# fsa1_psu.net
KiCad netlist of a schematic drawn in EAGLE
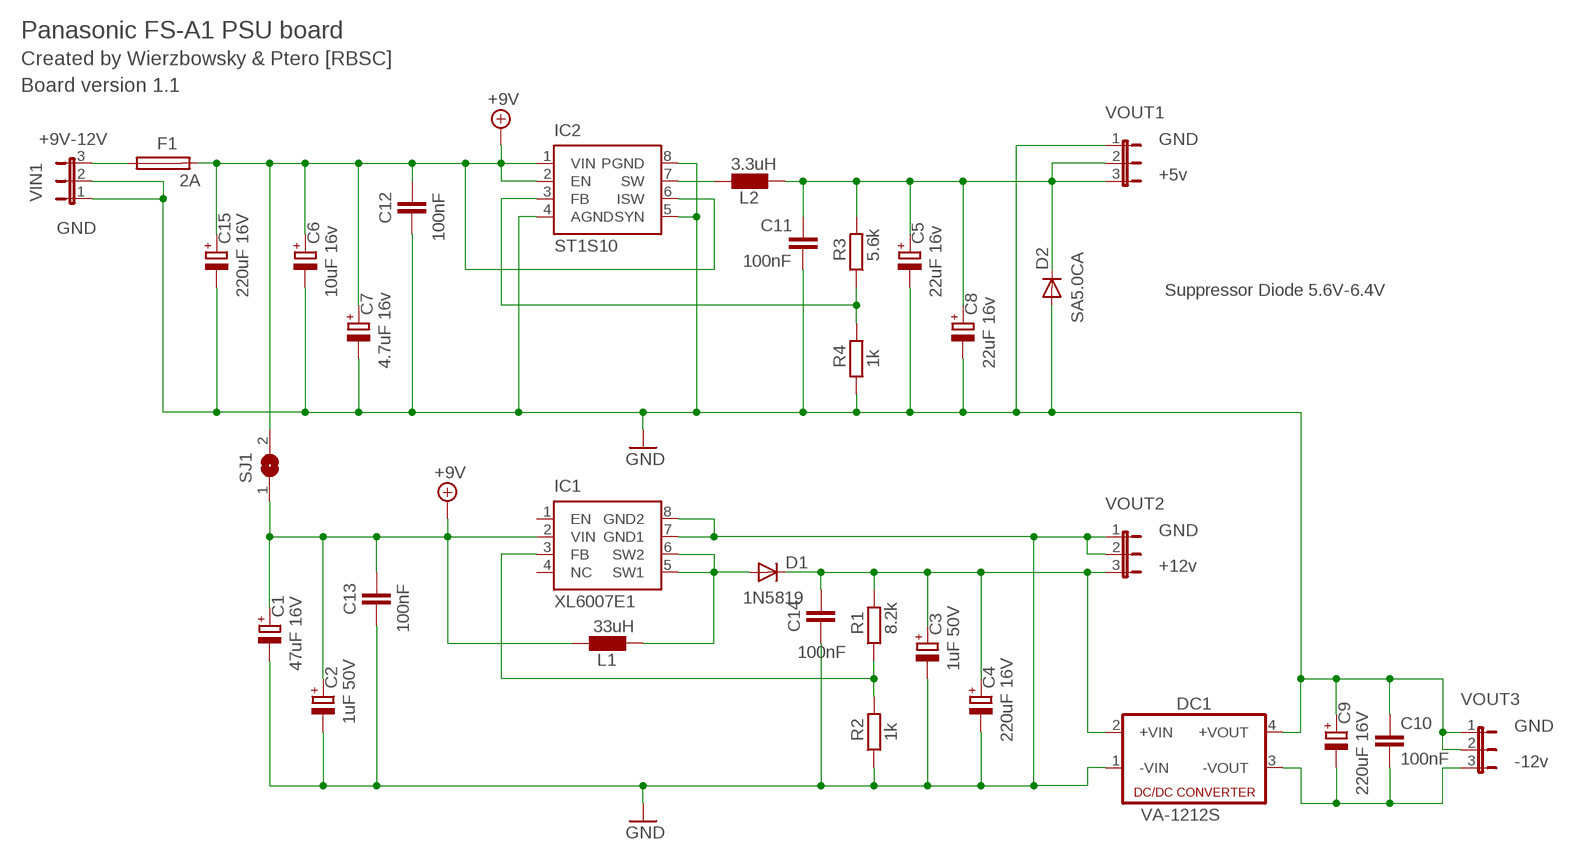
[diagram p0: schematic, sheet 1]

(export (version "E")
  (design (tool "Eeschema 10.0.6"))
  (components
    (comp (ref "C1")
      (value "47uF 16V")
      (footprint "eagle-import:SANYO-OSCON_C6")
      (libsource (lib "eagle-import") (part "CPOL-EUSANYO_C6"))
    )
    (comp (ref "C2")
      (value "1uF 50V")
      (footprint "eagle-import:SANYO-OSCON_C6")
      (libsource (lib "eagle-import") (part "CPOL-EUSANYO_C6"))
    )
    (comp (ref "C3")
      (value "1uF 50V")
      (footprint "eagle-import:SANYO-OSCON_C6")
      (libsource (lib "eagle-import") (part "CPOL-EUSANYO_C6"))
    )
    (comp (ref "C4")
      (value "220uF 16V")
      (footprint "eagle-import:SANYO-OSCON_E7")
      (libsource (lib "eagle-import") (part "CPOL-EUSANYO_E7"))
    )
    (comp (ref "C5")
      (value "22uF 16v")
      (footprint "eagle-import:SANYO-OSCON_C6")
      (libsource (lib "eagle-import") (part "CPOL-EUSANYO_C6"))
    )
    (comp (ref "C6")
      (value "10uF 16v")
      (footprint "eagle-import:SANYO-OSCON_C6")
      (libsource (lib "eagle-import") (part "CPOL-EUSANYO_C6"))
    )
    (comp (ref "C7")
      (value "4.7uF 16v")
      (footprint "eagle-import:SANYO-OSCON_C6")
      (libsource (lib "eagle-import") (part "CPOL-EUSANYO_C6"))
    )
    (comp (ref "C8")
      (value "22uF 16v")
      (footprint "eagle-import:SANYO-OSCON_C6")
      (libsource (lib "eagle-import") (part "CPOL-EUSANYO_C6"))
    )
    (comp (ref "C9")
      (value "220uF 16V")
      (footprint "eagle-import:SANYO-OSCON_E7")
      (libsource (lib "eagle-import") (part "CPOL-EUSANYO_E7"))
    )
    (comp (ref "C10")
      (value "100nF")
      (footprint "eagle-import:C0805")
      (libsource (lib "eagle-import") (part "C-EUC0805"))
    )
    (comp (ref "C11")
      (value "100nF")
      (footprint "eagle-import:C0805")
      (libsource (lib "eagle-import") (part "C-EUC0805"))
    )
    (comp (ref "C12")
      (value "100nF")
      (footprint "eagle-import:C0805")
      (libsource (lib "eagle-import") (part "C-EUC0805"))
    )
    (comp (ref "C13")
      (value "100nF")
      (footprint "eagle-import:C0805")
      (libsource (lib "eagle-import") (part "C-EUC0805"))
    )
    (comp (ref "C14")
      (value "100nF")
      (footprint "eagle-import:C0805")
      (libsource (lib "eagle-import") (part "C-EUC0805"))
    )
    (comp (ref "C15")
      (value "220uF 16V")
      (footprint "eagle-import:SANYO-OSCON_E7")
      (libsource (lib "eagle-import") (part "CPOL-EUSANYO_E7"))
    )
    (comp (ref "D1")
      (value "1N5819")
      (footprint "eagle-import:DO204-10")
      (libsource (lib "eagle-import") (part "DIODE-DO204-10"))
    )
    (comp (ref "D2")
      (value "SA5.0CA")
      (footprint "eagle-import:DO204-10")
      (libsource (lib "eagle-import") (part "DIODE-DO204-10"))
    )
    (comp (ref "DC1")
      (value "VA-1212S")
      (footprint "eagle-import:4SIL")
      (libsource (lib "eagle-import") (part "VA-?S1212"))
    )
    (comp (ref "F1")
      (value "2A")
      (footprint "eagle-import:PICOFUSE")
      (libsource (lib "eagle-import") (part "PICOFUSE"))
    )
    (comp (ref "IC1")
      (value "XL6007E1")
      (footprint "eagle-import:SOIC08")
      (libsource (lib "eagle-import") (part "XL6007E1-SOIC"))
    )
    (comp (ref "IC2")
      (value "ST1S10")
      (footprint "eagle-import:SOIC08")
      (libsource (lib "eagle-import") (part "ST1S10-SOIC"))
    )
    (comp (ref "L1")
      (value "33uH")
      (footprint "eagle-import:0204_7")
      (libsource (lib "eagle-import") (part "L0204/7"))
    )
    (comp (ref "L2")
      (value "3.3uH")
      (footprint "eagle-import:0204_7")
      (libsource (lib "eagle-import") (part "L0204/7"))
    )
    (comp (ref "R1")
      (value "8.2k")
      (footprint "eagle-import:0204_7")
      (libsource (lib "eagle-import") (part "R-EU_0204/7"))
    )
    (comp (ref "R2")
      (value "1k")
      (footprint "eagle-import:0204_7")
      (libsource (lib "eagle-import") (part "R-EU_0204/7"))
    )
    (comp (ref "R3")
      (value "5.6k")
      (footprint "eagle-import:0204_7")
      (libsource (lib "eagle-import") (part "R-EU_0204/7"))
    )
    (comp (ref "R4")
      (value "1k")
      (footprint "eagle-import:0204_7")
      (libsource (lib "eagle-import") (part "R-EU_0204/7"))
    )
    (comp (ref "SJ1") (value "SJ") (footprint "eagle-import:SJ") (libsource (lib "eagle-import") (part "SJ")))
    (comp (ref "VIN1")
      (value "JP2E_SP")
      (footprint "eagle-import:JP2")
      (libsource (lib "eagle-import") (part "JP2E_SP"))
    )
    (comp (ref "VOUT1")
      (value "JP2E_SP")
      (footprint "eagle-import:JP2")
      (libsource (lib "eagle-import") (part "JP2E_SP"))
    )
    (comp (ref "VOUT2")
      (value "JP2E_SP")
      (footprint "eagle-import:JP2")
      (libsource (lib "eagle-import") (part "JP2E_SP"))
    )
    (comp (ref "VOUT3")
      (value "JP2E_SP")
      (footprint "eagle-import:JP2")
      (libsource (lib "eagle-import") (part "JP2E_SP"))
    )
  )
  (nets
    (net (code "1") (name "+9V") (class "Default")
      (node (ref "C1") (pin "+") (pinfunction "+_+") (pintype "passive"))
      (node (ref "C12") (pin "1") (pinfunction "1_1") (pintype "passive"))
      (node (ref "C13") (pin "1") (pinfunction "1_1") (pintype "passive"))
      (node (ref "C15") (pin "+") (pinfunction "+_+") (pintype "passive"))
      (node (ref "C2") (pin "+") (pinfunction "+_+") (pintype "passive"))
      (node (ref "C6") (pin "+") (pinfunction "+_+") (pintype "passive"))
      (node (ref "C7") (pin "+") (pinfunction "+_+") (pintype "passive"))
      (node (ref "F1") (pin "2") (pinfunction "2_2") (pintype "passive"))
      (node (ref "IC1") (pin "2") (pinfunction "VIN_2") (pintype "power_in"))
      (node (ref "IC2") (pin "1") (pinfunction "VIN_1") (pintype "power_in"))
      (node (ref "IC2") (pin "2") (pinfunction "EN_2") (pintype "input"))
      (node (ref "IC2") (pin "6") (pinfunction "ISW_6") (pintype "power_in"))
      (node (ref "L1") (pin "1") (pinfunction "1_1") (pintype "passive"))
      (node (ref "SJ1") (pin "1") (pinfunction "1_1") (pintype "passive"))
      (node (ref "SJ1") (pin "2") (pinfunction "2_2") (pintype "passive"))
    )
    (net (code "2") (name "GND") (class "Default")
      (node (ref "C1") (pin "-") (pinfunction "-_-") (pintype "passive"))
      (node (ref "C10") (pin "1") (pinfunction "1_1") (pintype "passive"))
      (node (ref "C11") (pin "2") (pinfunction "2_2") (pintype "passive"))
      (node (ref "C12") (pin "2") (pinfunction "2_2") (pintype "passive"))
      (node (ref "C13") (pin "2") (pinfunction "2_2") (pintype "passive"))
      (node (ref "C14") (pin "2") (pinfunction "2_2") (pintype "passive"))
      (node (ref "C15") (pin "-") (pinfunction "-_-") (pintype "passive"))
      (node (ref "C2") (pin "-") (pinfunction "-_-") (pintype "passive"))
      (node (ref "C3") (pin "-") (pinfunction "-_-") (pintype "passive"))
      (node (ref "C4") (pin "-") (pinfunction "-_-") (pintype "passive"))
      (node (ref "C5") (pin "-") (pinfunction "-_-") (pintype "passive"))
      (node (ref "C6") (pin "-") (pinfunction "-_-") (pintype "passive"))
      (node (ref "C7") (pin "-") (pinfunction "-_-") (pintype "passive"))
      (node (ref "C8") (pin "-") (pinfunction "-_-") (pintype "passive"))
      (node (ref "C9") (pin "+") (pinfunction "+_+") (pintype "passive"))
      (node (ref "D2") (pin "A") (pinfunction "A_A") (pintype "passive"))
      (node (ref "DC1") (pin "1") (pinfunction "-VIN_1") (pintype "passive"))
      (node (ref "DC1") (pin "4") (pinfunction "+VOUT_4") (pintype "passive"))
      (node (ref "IC1") (pin "7") (pinfunction "GND1_7") (pintype "power_in"))
      (node (ref "IC1") (pin "8") (pinfunction "GND2_8") (pintype "power_in"))
      (node (ref "IC2") (pin "4") (pinfunction "AGND_4") (pintype "power_in"))
      (node (ref "IC2") (pin "5") (pinfunction "SYN_5") (pintype "output"))
      (node (ref "IC2") (pin "8") (pinfunction "PGND_8") (pintype "power_in"))
      (node (ref "R2") (pin "1") (pinfunction "1_1") (pintype "passive"))
      (node (ref "R4") (pin "1") (pinfunction "1_1") (pintype "passive"))
      (node (ref "VIN1") (pin "1") (pinfunction "1_1") (pintype "passive"))
      (node (ref "VIN1") (pin "2") (pinfunction "2_2") (pintype "passive"))
      (node (ref "VOUT1") (pin "1") (pinfunction "1_1") (pintype "passive"))
      (node (ref "VOUT2") (pin "1") (pinfunction "1_1") (pintype "passive"))
      (node (ref "VOUT2") (pin "2") (pinfunction "2_2") (pintype "passive"))
      (node (ref "VOUT3") (pin "1") (pinfunction "1_1") (pintype "passive"))
      (node (ref "VOUT3") (pin "2") (pinfunction "2_2") (pintype "passive"))
    )
    (net (code "3") (name "Net-(C11-Pad1)") (class "Default")
      (node (ref "C11") (pin "1") (pinfunction "1_1") (pintype "passive"))
      (node (ref "C5") (pin "+") (pinfunction "+_+") (pintype "passive"))
      (node (ref "C8") (pin "+") (pinfunction "+_+") (pintype "passive"))
      (node (ref "D2") (pin "C") (pinfunction "C_C") (pintype "passive"))
      (node (ref "L2") (pin "2") (pinfunction "2_2") (pintype "passive"))
      (node (ref "R3") (pin "2") (pinfunction "2_2") (pintype "passive"))
      (node (ref "VOUT1") (pin "2") (pinfunction "2_2") (pintype "passive"))
      (node (ref "VOUT1") (pin "3") (pinfunction "3_3") (pintype "passive"))
    )
    (net (code "4") (name "Net-(DC1-+VIN)") (class "Default")
      (node (ref "C14") (pin "1") (pinfunction "1_1") (pintype "passive"))
      (node (ref "C3") (pin "+") (pinfunction "+_+") (pintype "passive"))
      (node (ref "C4") (pin "+") (pinfunction "+_+") (pintype "passive"))
      (node (ref "D1") (pin "C") (pinfunction "C_C") (pintype "passive"))
      (node (ref "DC1") (pin "2") (pinfunction "+VIN_2") (pintype "passive"))
      (node (ref "R1") (pin "2") (pinfunction "2_2") (pintype "passive"))
      (node (ref "VOUT2") (pin "3") (pinfunction "3_3") (pintype "passive"))
    )
    (net (code "5") (name "Net-(DC1--VOUT)") (class "Default")
      (node (ref "C10") (pin "2") (pinfunction "2_2") (pintype "passive"))
      (node (ref "C9") (pin "-") (pinfunction "-_-") (pintype "passive"))
      (node (ref "DC1") (pin "3") (pinfunction "-VOUT_3") (pintype "passive"))
      (node (ref "VOUT3") (pin "3") (pinfunction "3_3") (pintype "passive"))
    )
    (net (code "6") (name "Net-(F1-Pad1)") (class "Default")
      (node (ref "F1") (pin "1") (pinfunction "1_1") (pintype "passive"))
      (node (ref "VIN1") (pin "3") (pinfunction "3_3") (pintype "passive"))
    )
    (net (code "7") (name "Net-(IC1-FB)") (class "Default")
      (node (ref "IC1") (pin "3") (pinfunction "FB_3") (pintype "bidirectional"))
      (node (ref "R1") (pin "1") (pinfunction "1_1") (pintype "passive"))
      (node (ref "R2") (pin "2") (pinfunction "2_2") (pintype "passive"))
    )
    (net (code "8") (name "Net-(IC1-SW1)") (class "Default")
      (node (ref "D1") (pin "A") (pinfunction "A_A") (pintype "passive"))
      (node (ref "IC1") (pin "5") (pinfunction "SW1_5") (pintype "power_in"))
      (node (ref "IC1") (pin "6") (pinfunction "SW2_6") (pintype "power_in"))
      (node (ref "L1") (pin "2") (pinfunction "2_2") (pintype "passive"))
    )
    (net (code "9") (name "Net-(IC2-FB)") (class "Default")
      (node (ref "IC2") (pin "3") (pinfunction "FB_3") (pintype "bidirectional"))
      (node (ref "R3") (pin "1") (pinfunction "1_1") (pintype "passive"))
      (node (ref "R4") (pin "2") (pinfunction "2_2") (pintype "passive"))
    )
    (net (code "10") (name "Net-(IC2-SW)") (class "Default")
      (node (ref "IC2") (pin "7") (pinfunction "SW_7") (pintype "power_in"))
      (node (ref "L2") (pin "1") (pinfunction "1_1") (pintype "passive"))
    )
    (net (code "11") (name "unconnected-(IC1-EN-Pad1)") (class "Default")
      (node (ref "IC1") (pin "1") (pinfunction "EN_1") (pintype "input"))
    )
    (net (code "12") (name "unconnected-(IC1-NC-Pad4)") (class "Default")
      (node (ref "IC1") (pin "4") (pinfunction "NC_4") (pintype "no_connect"))
    )
  )
)
